# Voeding.net
KiCad netlist of a schematic drawn in Altium Designer
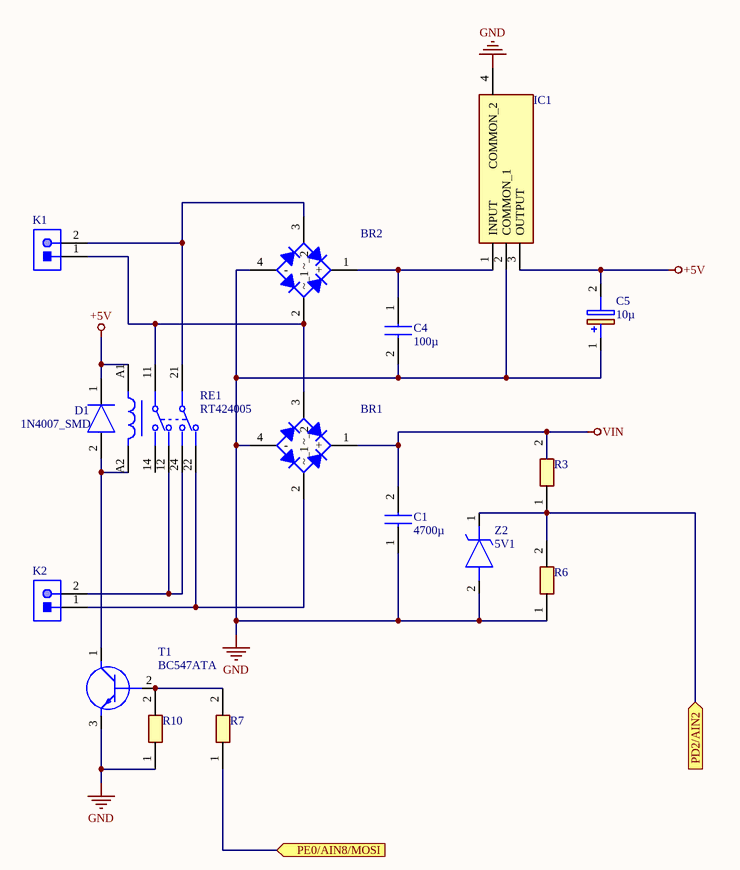
[diagram p0: Voeding.SchDoc]

(export (version "E")
  (design (tool "Eeschema 10.0.6"))
  (components
    (comp (ref "BR1")
      (value "GBU6J-E3_45")
      (footprint "SamacSys:GBU6JE345")
      (description "Bridge Rectifier")
      (fields (field (name "MANUFACTURER_PART_NUMBER") "GBU6J-E3/45"))
      (libsource (lib "SoldeerBoutLib") (part "GBU6J-E3_45"))
    )
    (comp (ref "BR2")
      (value "GBU6J-E3_45")
      (footprint "SamacSys:GBU6JE345")
      (description "Bridge Rectifier")
      (fields (field (name "MANUFACTURER_PART_NUMBER") "GBU6J-E3/45"))
      (libsource (lib "SoldeerBoutLib") (part "GBU6J-E3_45"))
    )
    (comp (ref "C1")
      (value "4700µ")
      (footprint "SamacSys:CAPPRD1000W80D2200H4100")
      (description "Capacitor")
      (fields
        (field (name "MANUFACTURER_PART_NUMBER") "860010683032")
        (field (name "MOUSER PART NUMBER") "710-860010683032")
      )
      (libsource (lib "*") (part "860010683032"))
    )
    (comp (ref "C4")
      (value "100µ")
      (footprint "SamacSys:CAPPRD350W52D800H1300")
      (description "Capacitor")
      (fields
        (field (name "MANUFACTURER_PART_NUMBER") "860010674014")
        (field (name "MOUSER PART NUMBER") "710-860010674014")
      )
      (libsource (lib "SoldeerBoutLib") (part "860010674014"))
    )
    (comp (ref "C5")
      (value "10µ")
      (footprint "SamacSys:CAPPRD200W52D500H1250")
      (description "Capacitor Polarised")
      (fields
        (field (name "MANUFACTURER_PART_NUMBER") "860010672009")
        (field (name "MOUSER PART NUMBER") "710-860010672009")
      )
      (libsource (lib "*") (part "860010672009"))
    )
    (comp (ref "D1")
      (value "1N4007_SMD")
      (footprint "SamacSys:DIOM5027X262N")
      (description "Diode")
      (fields (field (name "MANUFACTURER_PART_NUMBER") "1N4007 SMD"))
      (libsource (lib "SoldeerBoutLib") (part "1N4007_SMD"))
    )
    (comp (ref "IC1")
      (value "TL780-05CKTTR")
      (footprint "SamacSys:TL78005CKTTR")
      (description "Integrated Circuit")
      (fields (field (name "MOUSER PART NUMBER") "595-TL780-05CKTTR"))
      (libsource (lib "*") (part "TL780-05CKTTR"))
    )
    (comp (ref "K1")
      (value "620102131822")
      (footprint "620102131822")
      (description "Male Shrouded Header WR-WTB, SMT, Right Angled, pitch 2 mm, 1 x 2 position")
      (fields (field (name "MANUFACTURER") "Wurth Elektronik") (field (name "PUBLISHER") "WurthElektronik"))
      (libsource (lib "Altium Content Vault") (part "WE-CN-1P-M-R2"))
    )
    (comp (ref "K2")
      (value "620102131822")
      (footprint "620102131822")
      (description "Male Shrouded Header WR-WTB, SMT, Right Angled, pitch 2 mm, 1 x 2 position")
      (fields (field (name "MANUFACTURER") "Wurth Elektronik") (field (name "PUBLISHER") "WurthElektronik"))
      (libsource (lib "Altium Content Vault") (part "WE-CN-1P-M-R2"))
    )
    (comp (ref "R3")
      (value "~")
      (footprint "SamacSys:RESC2012X90N")
      (description "Resistor")
      (fields (field (name "MANUFACTURER_PART_NUMBER") "CFN0805-JZ-R010ELF"))
      (libsource (lib "SoldeerBoutLib") (part "CFN0805-JZ-R010ELF"))
    )
    (comp (ref "R6")
      (value "~")
      (footprint "SamacSys:RESC2012X90N")
      (description "Resistor")
      (fields (field (name "MANUFACTURER_PART_NUMBER") "CFN0805-JZ-R010ELF"))
      (libsource (lib "SoldeerBoutLib") (part "CFN0805-JZ-R010ELF"))
    )
    (comp (ref "R7")
      (value "~")
      (footprint "SamacSys:RESC2012X90N")
      (description "Resistor")
      (fields (field (name "MANUFACTURER_PART_NUMBER") "CFN0805-JZ-R010ELF"))
      (libsource (lib "SoldeerBoutLib") (part "CFN0805-JZ-R010ELF"))
    )
    (comp (ref "R10")
      (value "~")
      (footprint "SamacSys:RESC2012X90N")
      (description "Resistor")
      (fields (field (name "MANUFACTURER_PART_NUMBER") "CFN0805-JZ-R010ELF"))
      (libsource (lib "SoldeerBoutLib") (part "CFN0805-JZ-R010ELF"))
    )
    (comp (ref "RE1")
      (value "RT424005")
      (footprint "SamacSys:RT42")
      (description "Relay or Contactor")
      (fields (field (name "MOUSER PART NUMBER") "655-RT424005"))
      (libsource (lib "SoldeerBoutLib") (part "RT424005"))
    )
    (comp (ref "T1")
      (value "BC547ATA")
      (footprint "SamacSys:TO-92_(TO-226)")
      (description "Transistor BJT NPN")
      (fields (field (name "MOUSER PART NUMBER") "512-BC547ATA"))
      (libsource (lib "*") (part "BC547ATA"))
    )
    (comp (ref "Z2")
      (value "5V1")
      (footprint "SamacSys:SODFL1608X65N")
      (description "Zener Diode")
      (fields
        (field (name "MANUFACTURER_PART_NUMBER") "BZT52C12TQ-7-F")
        (field (name "MOUSER PART NUMBER") "621-BZT52C12TQ-7-F")
      )
      (libsource (lib "SoldeerBoutLib") (part "BZT52C12TQ-7-F"))
    )
  )
  (nets
    (net (code "1") (name "+5V") (class "Default")
      (node (ref "C5") (pin "2") (pinfunction "-_2") (pintype "passive"))
      (node (ref "D1") (pin "1") (pinfunction "K_1") (pintype "passive"))
      (node (ref "IC1") (pin "3") (pinfunction "OUTPUT_3") (pintype "passive"))
      (node (ref "RE1") (pin "A1") (pinfunction "A1_A1") (pintype "passive"))
    )
    (net (code "2") (name "/PD2{slash}AIN2") (class "Default")
      (node (ref "R3") (pin "1") (pinfunction "1_1") (pintype "passive"))
      (node (ref "R6") (pin "2") (pinfunction "2_2") (pintype "passive"))
      (node (ref "Z2") (pin "1") (pinfunction "K_1") (pintype "passive"))
    )
    (net (code "3") (name "/PE0{slash}AIN8{slash}MOSI") (class "Default")
      (node (ref "R7") (pin "1") (pinfunction "1_1") (pintype "passive"))
    )
    (net (code "4") (name "GND") (class "Default")
      (node (ref "BR1") (pin "4") (pinfunction "-_4") (pintype "passive"))
      (node (ref "BR2") (pin "4") (pinfunction "-_4") (pintype "passive"))
      (node (ref "C1") (pin "1") (pinfunction "+_1") (pintype "power_in"))
      (node (ref "C4") (pin "2") (pinfunction "-_2") (pintype "passive"))
      (node (ref "C5") (pin "1") (pinfunction "+_1") (pintype "passive"))
      (node (ref "IC1") (pin "2") (pinfunction "COMMON_1_2") (pintype "passive"))
      (node (ref "IC1") (pin "4") (pinfunction "COMMON_2_4") (pintype "passive"))
      (node (ref "R10") (pin "1") (pinfunction "1_1") (pintype "passive"))
      (node (ref "R6") (pin "1") (pinfunction "1_1") (pintype "passive"))
      (node (ref "T1") (pin "3") (pinfunction "E_3") (pintype "passive"))
      (node (ref "Z2") (pin "2") (pinfunction "A_2") (pintype "passive"))
    )
    (net (code "5") (name "Net-(BR1-~_1)") (class "Default")
      (node (ref "BR1") (pin "2") (pinfunction "~_1_2") (pintype "passive"))
      (node (ref "K2") (pin "1") (pinfunction "1_1") (pintype "passive"))
      (node (ref "RE1") (pin "22") (pinfunction "22_22") (pintype "passive"))
    )
    (net (code "6") (name "Net-(BR1-~_2)") (class "Default")
      (node (ref "BR1") (pin "3") (pinfunction "~_2_3") (pintype "passive"))
      (node (ref "BR2") (pin "2") (pinfunction "~_1_2") (pintype "passive"))
      (node (ref "K1") (pin "1") (pinfunction "1_1") (pintype "passive"))
      (node (ref "RE1") (pin "11") (pinfunction "11_11") (pintype "passive"))
    )
    (net (code "7") (name "Net-(BR2-+)") (class "Default")
      (node (ref "BR2") (pin "1") (pinfunction "+_1") (pintype "passive"))
      (node (ref "C4") (pin "1") (pinfunction "+_1") (pintype "passive"))
      (node (ref "IC1") (pin "1") (pinfunction "INPUT_1") (pintype "passive"))
    )
    (net (code "8") (name "Net-(BR2-~_2)") (class "Default")
      (node (ref "BR2") (pin "3") (pinfunction "~_2_3") (pintype "passive"))
      (node (ref "K1") (pin "2") (pinfunction "2_2") (pintype "passive"))
      (node (ref "RE1") (pin "21") (pinfunction "21_21") (pintype "passive"))
    )
    (net (code "9") (name "Net-(D1-A)") (class "Default")
      (node (ref "D1") (pin "2") (pinfunction "A_2") (pintype "passive"))
      (node (ref "RE1") (pin "A2") (pinfunction "A2_A2") (pintype "passive"))
      (node (ref "T1") (pin "1") (pinfunction "C_1") (pintype "passive"))
    )
    (net (code "10") (name "Net-(K2-Pad2)") (class "Default")
      (node (ref "K2") (pin "2") (pinfunction "2_2") (pintype "passive"))
      (node (ref "RE1") (pin "12") (pinfunction "12_12") (pintype "passive"))
      (node (ref "RE1") (pin "24") (pinfunction "24_24") (pintype "passive"))
    )
    (net (code "11") (name "Net-(T1-B)") (class "Default")
      (node (ref "R10") (pin "2") (pinfunction "2_2") (pintype "passive"))
      (node (ref "R7") (pin "2") (pinfunction "2_2") (pintype "passive"))
      (node (ref "T1") (pin "2") (pinfunction "B_2") (pintype "passive"))
    )
    (net (code "12") (name "VIN") (class "Default")
      (node (ref "BR1") (pin "1") (pinfunction "+_1") (pintype "passive"))
      (node (ref "C1") (pin "2") (pinfunction "-_2") (pintype "power_in"))
      (node (ref "R3") (pin "2") (pinfunction "2_2") (pintype "passive"))
    )
    (net (code "13") (name "unconnected-(RE1-Pad14)") (class "Default")
      (node (ref "RE1") (pin "14") (pinfunction "14_14") (pintype "passive"))
    )
  )
)
